# Schematic2.net
KiCad netlist of a schematic drawn in Altium Designer
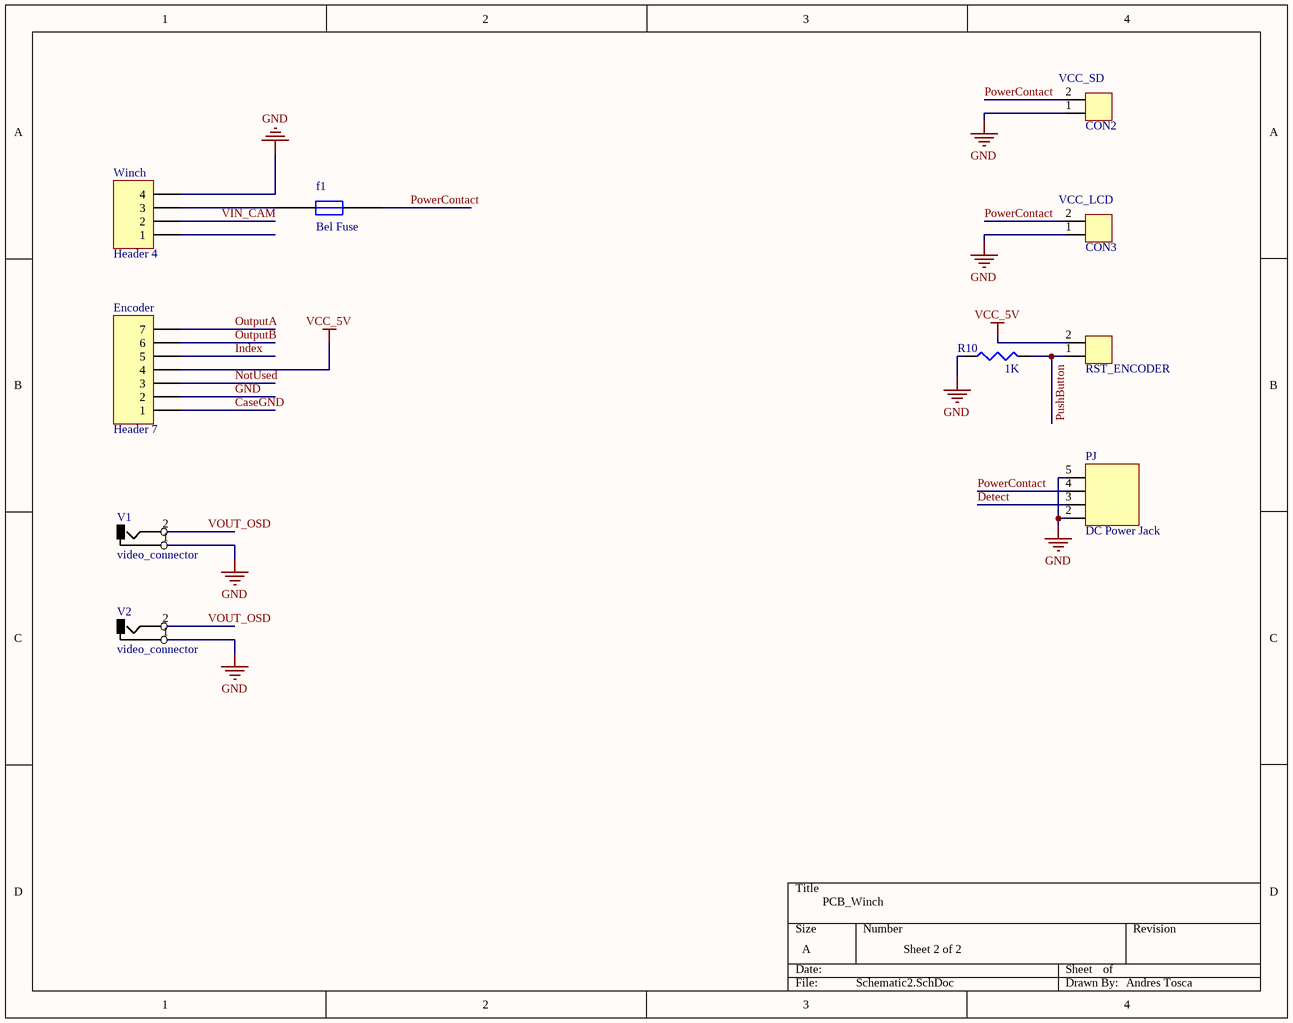
[diagram p0: Schematic2.SchDoc]

(export (version "E")
  (design (tool "Eeschema 10.0.6"))
  (components
    (comp (ref "CON2")
      (value "VCC_SD")
      (footprint "MOLEX_2CIRCUITS")
      (libsource (lib "Schlib") (part "MOLEX_2circuits"))
    )
    (comp (ref "CON3")
      (value "VCC_LCD")
      (footprint "MOLEX_2CIRCUITS")
      (libsource (lib "Schlib") (part "MOLEX_2circuits"))
    )
    (comp (ref "Encoder")
      (value "Header 7")
      (footprint "MOLEX_7CIRCUITS")
      (description "Header, 7-Pin")
      (fields (field (name "PUBLISHER") "Altium Limited"))
      (libsource (lib "Miscellaneous Connectors") (part "Header 7"))
    )
    (comp (ref "f1") (value "Bel Fuse") (footprint "Bel_Fuse") (libsource (lib "Schlib") (part "Bel Fuse")))
    (comp (ref "PJ")
      (value "DC Power Jack")
      (footprint "DC Power Jack TE")
      (libsource (lib "Schlib") (part "DC Power Jack TE"))
    )
    (comp (ref "R10")
      (value "1K")
      (footprint "RESC2012")
      (description "Resistor")
      (fields (field (name "Comment") "Res3") (field (name "PUBLISHER") "Altium Limited"))
      (libsource (lib "Miscellaneous Devices") (part "Res3"))
    )
    (comp (ref "RST_ENCODER")
      (value "MOLEX_2circuits")
      (footprint "MOLEX_2CIRCUITS")
      (libsource (lib "Schlib") (part "MOLEX_2circuits"))
    )
    (comp (ref "V1")
      (value "video_connector")
      (footprint "Video Connector")
      (libsource (lib "Schlib") (part "video_connector"))
    )
    (comp (ref "V2")
      (value "video_connector")
      (footprint "Video Connector")
      (libsource (lib "Schlib") (part "video_connector"))
    )
    (comp (ref "Winch")
      (value "Header 4")
      (footprint "MOLEX_4CIRCUITS")
      (description "Header, 4-Pin")
      (fields (field (name "PUBLISHER") "Altium Limited"))
      (libsource (lib "Miscellaneous Connectors") (part "Header 4"))
    )
  )
  (nets
    (net (code "1") (name "/CaseGND") (class "Default")
      (node (ref "Encoder") (pin "1") (pinfunction "1_1") (pintype "passive"))
    )
    (net (code "2") (name "/Detect") (class "Default")
      (node (ref "PJ") (pin "3") (pinfunction "3_3") (pintype "passive"))
    )
    (net (code "3") (name "/Index") (class "Default")
      (node (ref "Encoder") (pin "5") (pinfunction "5_5") (pintype "passive"))
    )
    (net (code "4") (name "/NotUsed") (class "Default")
      (node (ref "Encoder") (pin "3") (pinfunction "3_3") (pintype "passive"))
    )
    (net (code "5") (name "/OutputA") (class "Default")
      (node (ref "Encoder") (pin "7") (pinfunction "7_7") (pintype "passive"))
    )
    (net (code "6") (name "/OutputB") (class "Default")
      (node (ref "Encoder") (pin "6") (pinfunction "6_6") (pintype "passive"))
    )
    (net (code "7") (name "/PowerContact") (class "Default")
      (node (ref "CON2") (pin "2") (pinfunction "2_2") (pintype "passive"))
      (node (ref "CON3") (pin "2") (pinfunction "2_2") (pintype "passive"))
      (node (ref "PJ") (pin "4") (pinfunction "4_4") (pintype "passive"))
      (node (ref "f1") (pin "2") (pinfunction "2_2") (pintype "passive"))
    )
    (net (code "8") (name "/PushButton") (class "Default")
      (node (ref "R10") (pin "2") (pinfunction "2_2") (pintype "passive"))
      (node (ref "RST_ENCODER") (pin "1") (pinfunction "1_1") (pintype "passive"))
    )
    (net (code "9") (name "/VIN_CAM") (class "Default")
      (node (ref "Winch") (pin "2") (pinfunction "2_2") (pintype "passive"))
    )
    (net (code "10") (name "/VOUT_OSD") (class "Default")
      (node (ref "V1") (pin "2") (pinfunction "2_2") (pintype "passive"))
      (node (ref "V2") (pin "2") (pinfunction "2_2") (pintype "passive"))
    )
    (net (code "11") (name "GND") (class "Default")
      (node (ref "CON2") (pin "1") (pinfunction "1_1") (pintype "passive"))
      (node (ref "CON3") (pin "1") (pinfunction "1_1") (pintype "passive"))
      (node (ref "Encoder") (pin "2") (pinfunction "2_2") (pintype "passive"))
      (node (ref "PJ") (pin "2") (pinfunction "2_2") (pintype "passive"))
      (node (ref "PJ") (pin "5") (pinfunction "5_5") (pintype "passive"))
      (node (ref "R10") (pin "1") (pinfunction "1_1") (pintype "passive"))
      (node (ref "V1") (pin "1") (pinfunction "1_1") (pintype "passive"))
      (node (ref "V2") (pin "1") (pinfunction "1_1") (pintype "passive"))
      (node (ref "Winch") (pin "4") (pinfunction "4_4") (pintype "passive"))
    )
    (net (code "12") (name "Net-(Winch-Pad3)") (class "Default")
      (node (ref "Winch") (pin "3") (pinfunction "3_3") (pintype "passive"))
      (node (ref "f1") (pin "1") (pinfunction "1_1") (pintype "passive"))
    )
    (net (code "13") (name "VCC_5V") (class "Default")
      (node (ref "Encoder") (pin "4") (pinfunction "4_4") (pintype "passive"))
      (node (ref "RST_ENCODER") (pin "2") (pinfunction "2_2") (pintype "passive"))
    )
    (net (code "14") (name "unconnected-(Winch-Pad1)") (class "Default")
      (node (ref "Winch") (pin "1") (pinfunction "1_1") (pintype "passive"))
    )
  )
)
